# Sheet2.net
KiCad netlist of a schematic drawn in Altium Designer
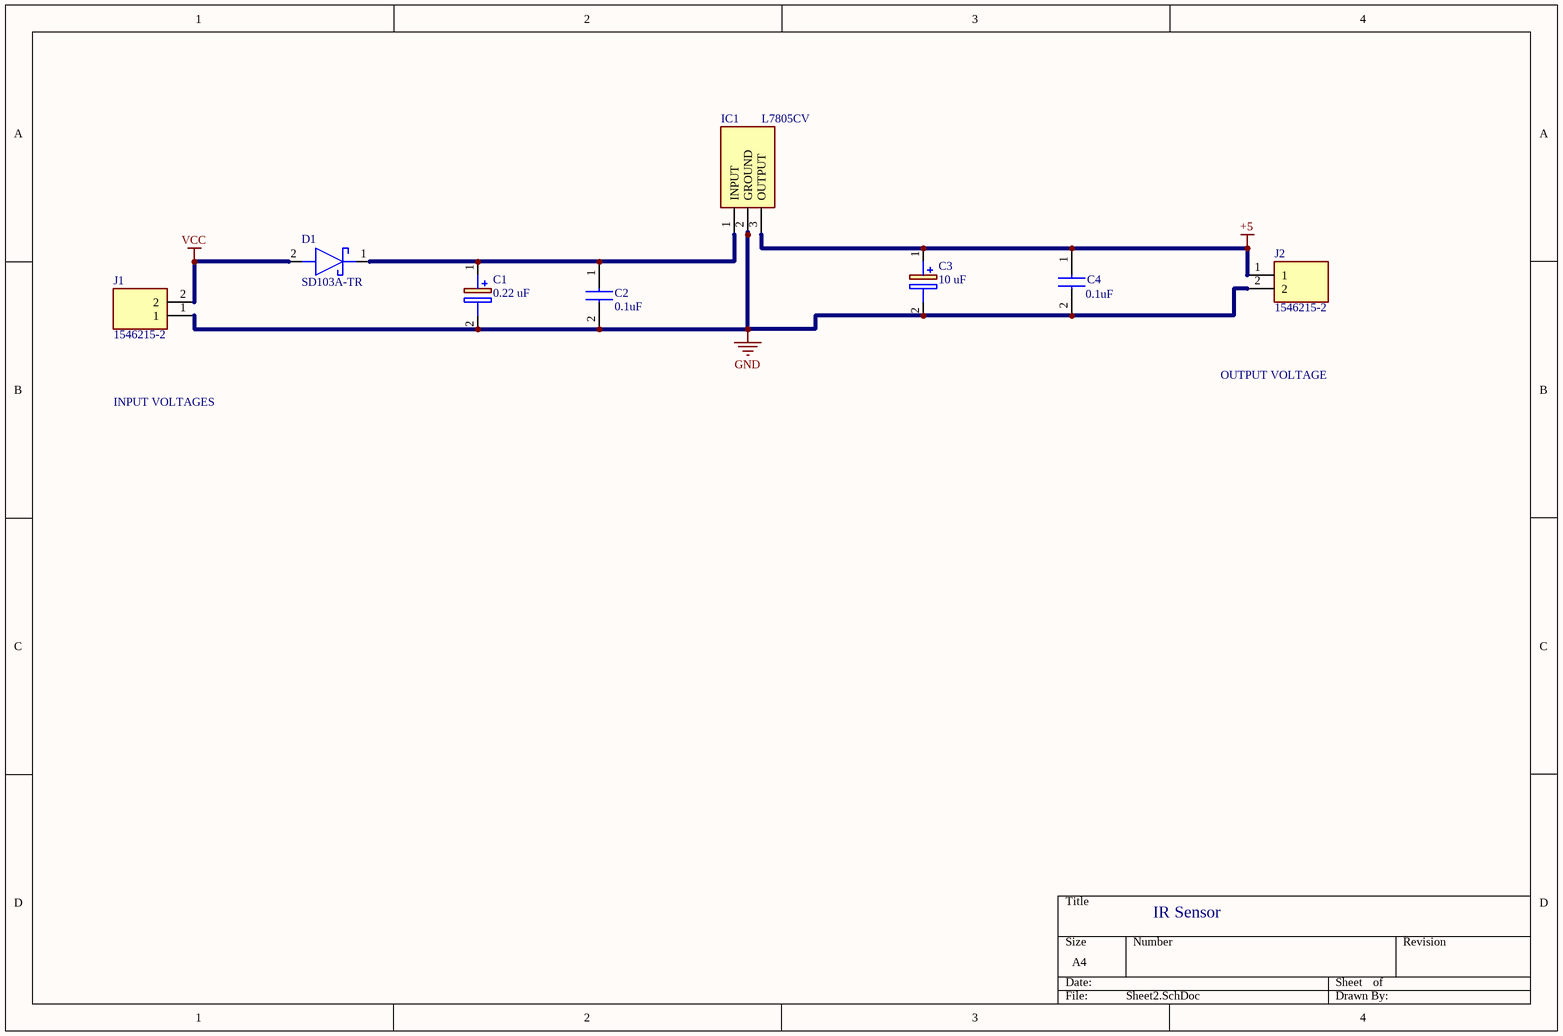
[diagram p0: Sheet2.SchDoc]

(export (version "E")
  (design (tool "Eeschema 10.0.6"))
  (components
    (comp (ref "C1")
      (value "0.22 uF")
      (footprint "SamacSys:CAPPRD200W52D500H1250")
      (description "Capacitor Polarised")
      (fields
        (field (name "MANUFACTURER_PART_NUMBER") "860010772002")
        (field (name "MOUSER PART NUMBER") "710-860010772002")
      )
      (libsource (lib "*") (part "860010772002"))
    )
    (comp (ref "C2")
      (value "0.1uF")
      (footprint "SamacSys:RDER71E104K0P1H03B")
      (description "Capacitor")
      (fields
        (field (name "MANUFACTURER_PART_NUMBER") "RDER71E104K0P1H03B")
        (field (name "MOUSER PART NUMBER") "81-RDER71E104K0P1H3B")
      )
      (libsource (lib "*") (part "RDER71E104K0P1H03B"))
    )
    (comp (ref "C3")
      (value "10 uF")
      (footprint "SamacSys:CAPPRD200W55D500H1250")
      (description "Capacitor Polarised")
      (fields
        (field (name "MANUFACTURER_PART_NUMBER") "EEU-FR1H100")
        (field (name "MOUSER PART NUMBER") "667-EEU-FR1H100")
      )
      (libsource (lib "*") (part "EEU-FR1H100"))
    )
    (comp (ref "C4")
      (value "0.1uF")
      (footprint "SamacSys:RDER71E104K0P1H03B")
      (description "Capacitor")
      (fields
        (field (name "MANUFACTURER_PART_NUMBER") "RDER71E104K0P1H03B")
        (field (name "MOUSER PART NUMBER") "81-RDER71E104K0P1H3B")
      )
      (libsource (lib "*") (part "RDER71E104K0P1H03B"))
    )
    (comp (ref "D1")
      (value "SD103A-TR")
      (footprint "SamacSys:DIOAD950W60L350D150")
      (description "Schottky Diode")
      (fields (field (name "MOUSER PART NUMBER") "625-SD103A"))
      (libsource (lib "*") (part "SD103A-TR"))
    )
    (comp (ref "IC1")
      (value "L7805CV")
      (footprint "SamacSys:TO255P460X1020X2008-3P")
      (description "Integrated Circuit")
      (fields (field (name "MOUSER PART NUMBER") "511-L7805CV"))
      (libsource (lib "*") (part "L7805CV"))
    )
    (comp (ref "J1")
      (value "1546215-2")
      (footprint "SamacSys:15462152")
      (description "Connector")
      (fields (field (name "MOUSER PART NUMBER") "571-1546215-2"))
      (libsource (lib "") (part "1546215-2_1"))
    )
    (comp (ref "J2")
      (value "1546215-2")
      (footprint "SamacSys:15462152")
      (description "Connector")
      (fields (field (name "MOUSER PART NUMBER") "571-1546215-2"))
      (libsource (lib "*") (part "1546215-2"))
    )
  )
  (nets
    (net (code "1") (name "+5") (class "Default")
      (node (ref "C3") (pin "1") (pinfunction "+_1") (pintype "power_in"))
      (node (ref "C4") (pin "1") (pinfunction "1_1") (pintype "passive"))
      (node (ref "IC1") (pin "3") (pinfunction "OUTPUT_3") (pintype "passive"))
      (node (ref "J2") (pin "1") (pinfunction "1_1") (pintype "passive"))
    )
    (net (code "2") (name "GND") (class "Default")
      (node (ref "C1") (pin "2") (pinfunction "-_2") (pintype "passive"))
      (node (ref "C2") (pin "2") (pinfunction "2_2") (pintype "passive"))
      (node (ref "C3") (pin "2") (pinfunction "-_2") (pintype "power_in"))
      (node (ref "C4") (pin "2") (pinfunction "2_2") (pintype "passive"))
      (node (ref "IC1") (pin "2") (pinfunction "GROUND_2") (pintype "passive"))
      (node (ref "J1") (pin "1") (pinfunction "1_1") (pintype "passive"))
      (node (ref "J2") (pin "2") (pinfunction "2_2") (pintype "passive"))
    )
    (net (code "3") (name "Net-(C1-+)") (class "Default")
      (node (ref "C1") (pin "1") (pinfunction "+_1") (pintype "passive"))
      (node (ref "C2") (pin "1") (pinfunction "1_1") (pintype "passive"))
      (node (ref "D1") (pin "1") (pinfunction "K_1") (pintype "passive"))
      (node (ref "IC1") (pin "1") (pinfunction "INPUT_1") (pintype "passive"))
    )
    (net (code "4") (name "VCC") (class "Default")
      (node (ref "D1") (pin "2") (pinfunction "A_2") (pintype "passive"))
      (node (ref "J1") (pin "2") (pinfunction "2_2") (pintype "passive"))
    )
  )
)
